# f280049_boost_robotics.net
KiCad netlist of a schematic drawn in EAGLE
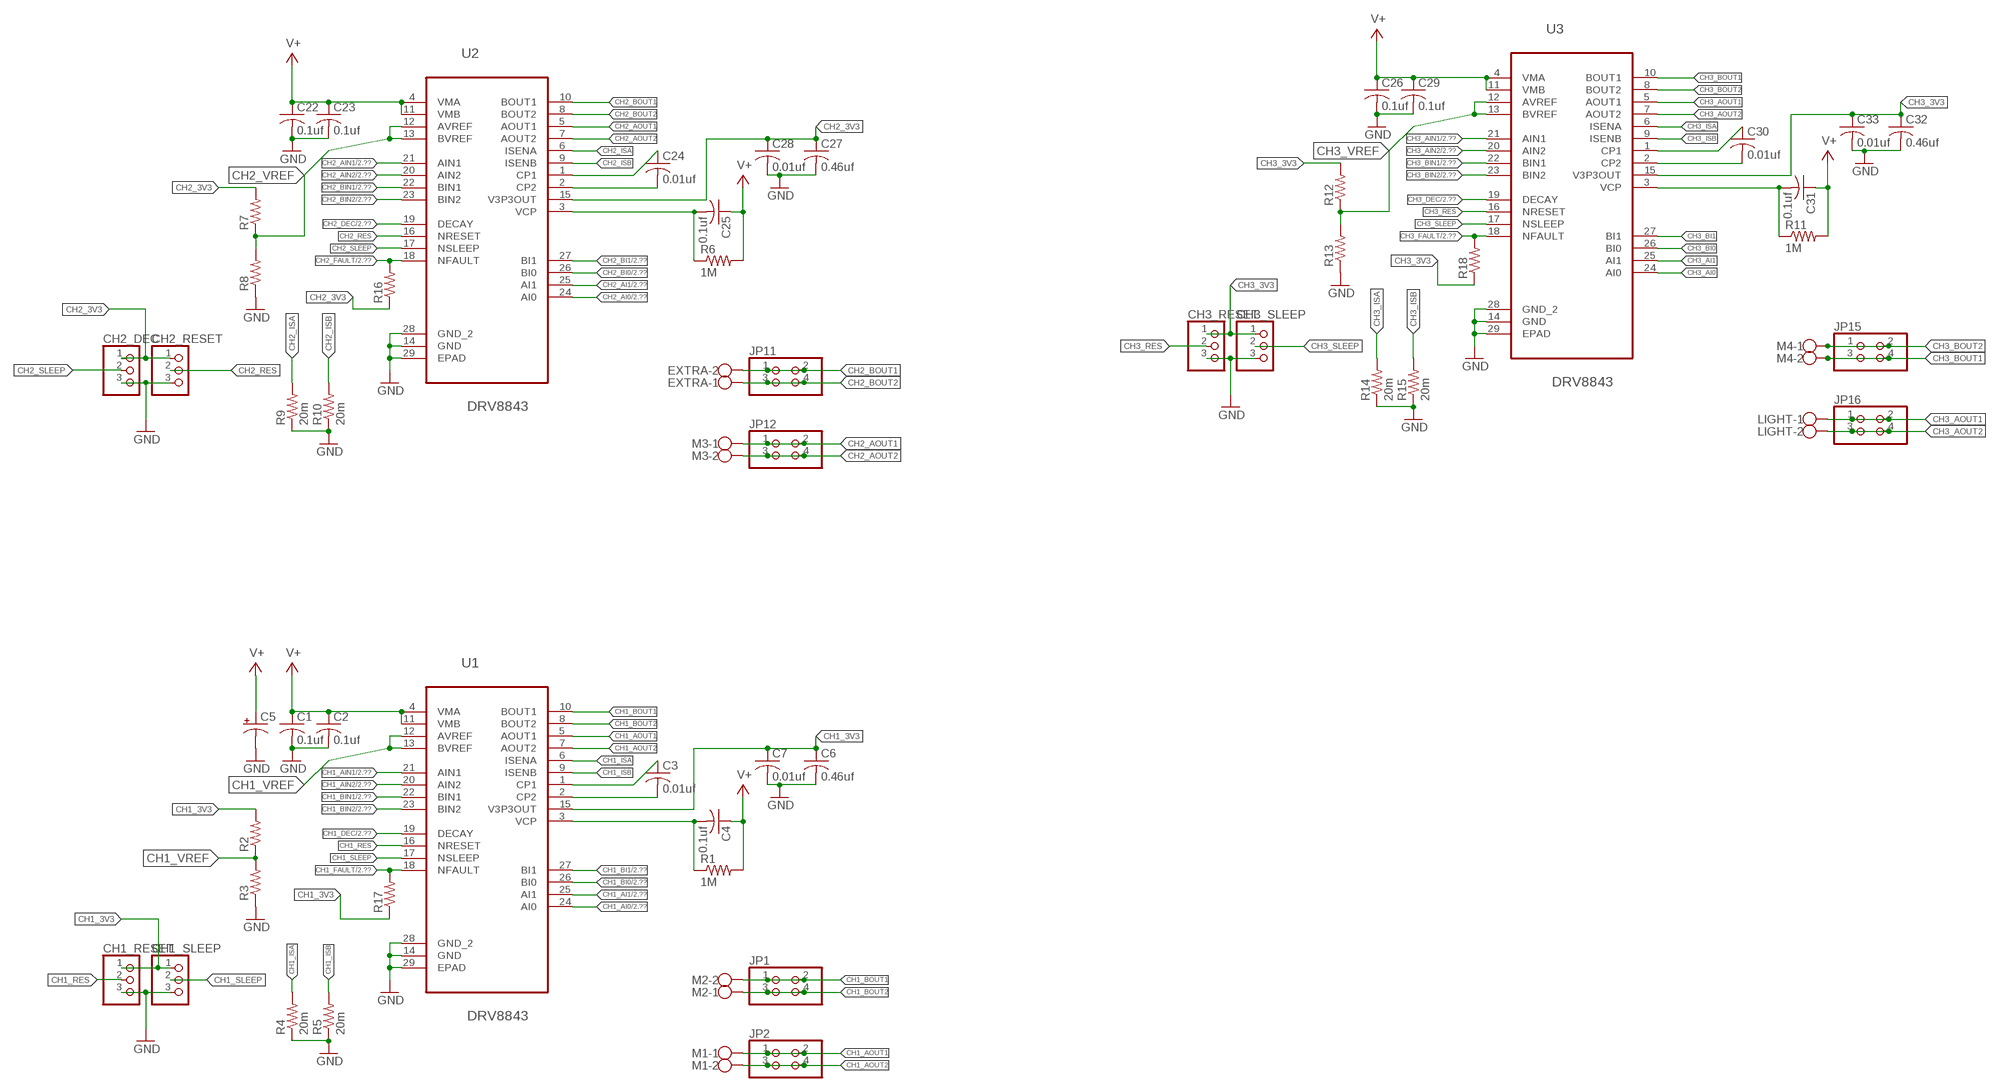
[diagram p0: schematic, sheet 1]
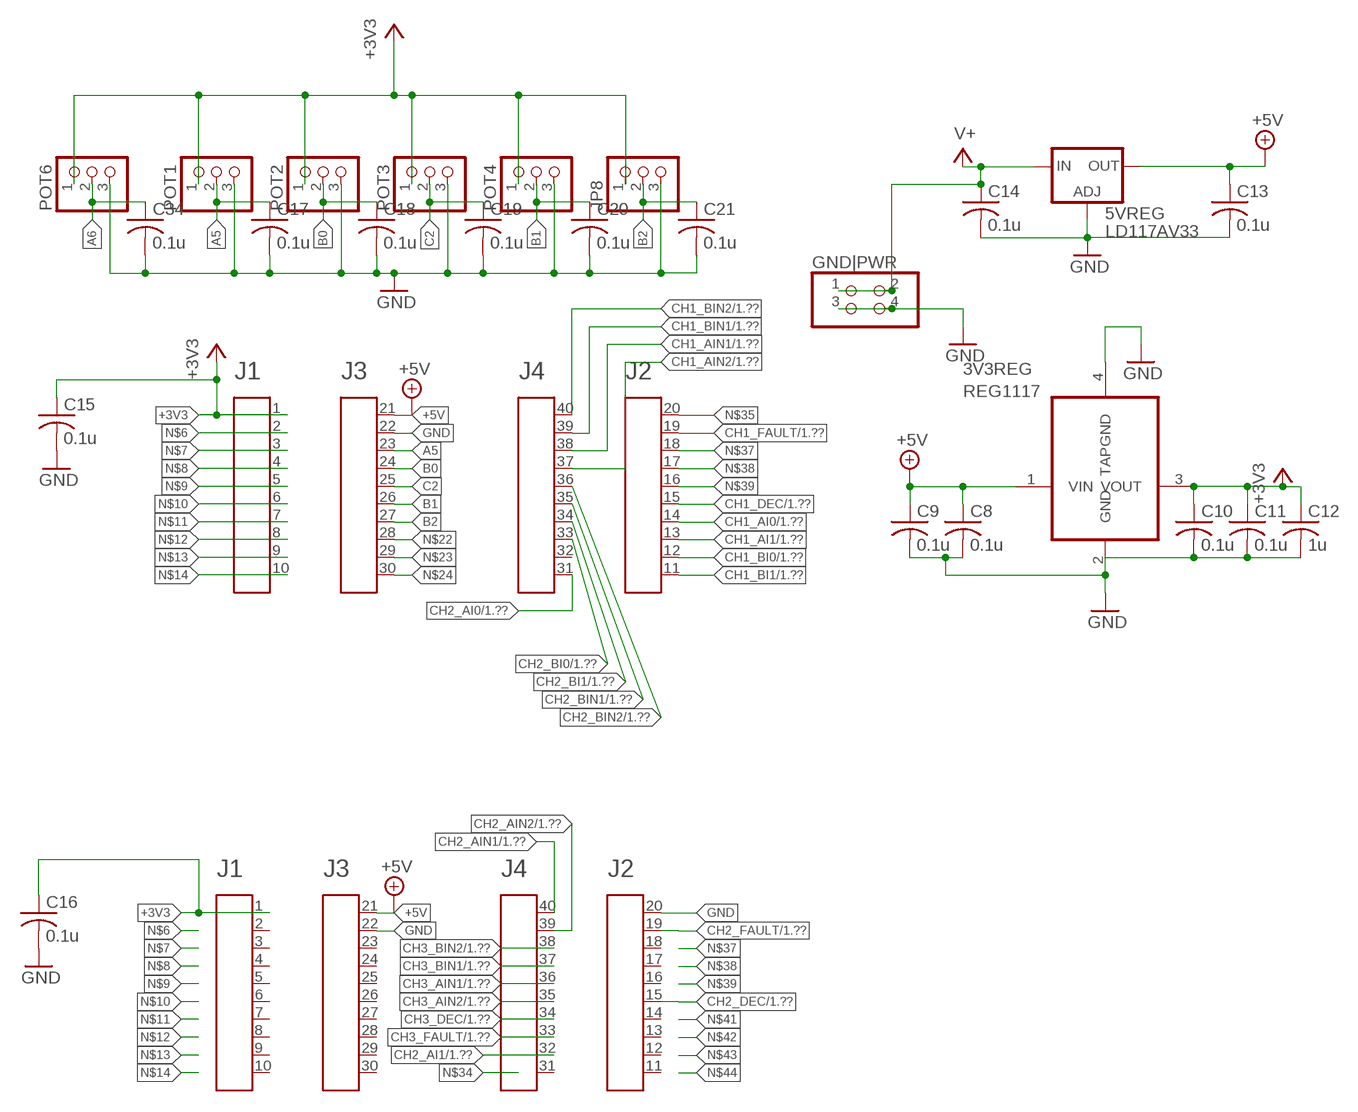
[diagram p1: schematic, sheet 2]

(export (version "E")
  (design (tool "Eeschema 10.0.6"))
  (components
    (comp (ref "3V3REG")
      (value "REG1117")
      (footprint "eagle-import:SOT223")
      (libsource (lib "eagle-import") (part "REG1117"))
    )
    (comp (ref "5VREG")
      (value "LD117AV33")
      (footprint "eagle-import:TO220L1")
      (libsource (lib "eagle-import") (part "LD117A?V33"))
    )
    (comp (ref "A1")
      (value "HEADER4X10-BOOSTERPACK")
      (footprint "eagle-import:4X10-BOOSTERPACK")
      (libsource (lib "eagle-import") (part "HEADER4X10-BOOSTERPACK"))
    )
    (comp (ref "A2")
      (value "HEADER4X10-BOOSTERPACK")
      (footprint "eagle-import:4X10-BOOSTERPACK")
      (libsource (lib "eagle-import") (part "HEADER4X10-BOOSTERPACK"))
    )
    (comp (ref "C8")
      (value "0.1u")
      (footprint "eagle-import:C0603K")
      (libsource (lib "eagle-import") (part "C-USC0603K"))
    )
    (comp (ref "C9")
      (value "0.1u")
      (footprint "eagle-import:C0603K")
      (libsource (lib "eagle-import") (part "C-USC0603K"))
    )
    (comp (ref "C10")
      (value "0.1u")
      (footprint "eagle-import:C0603K")
      (libsource (lib "eagle-import") (part "C-USC0603K"))
    )
    (comp (ref "C11")
      (value "0.1u")
      (footprint "eagle-import:C0603K")
      (libsource (lib "eagle-import") (part "C-USC0603K"))
    )
    (comp (ref "C12")
      (value "1u")
      (footprint "eagle-import:C0805K")
      (libsource (lib "eagle-import") (part "C-USC0805K"))
    )
    (comp (ref "C13")
      (value "0.1u")
      (footprint "eagle-import:C0603K")
      (libsource (lib "eagle-import") (part "C-USC0603K"))
    )
    (comp (ref "C14")
      (value "0.1u")
      (footprint "eagle-import:C0603K")
      (libsource (lib "eagle-import") (part "C-USC0603K"))
    )
    (comp (ref "C15")
      (value "0.1u")
      (footprint "eagle-import:C0603K")
      (libsource (lib "eagle-import") (part "C-USC0603K"))
    )
    (comp (ref "C16")
      (value "0.1u")
      (footprint "eagle-import:C0603K")
      (libsource (lib "eagle-import") (part "C-USC0603K"))
    )
    (comp (ref "C17")
      (value "0.1u")
      (footprint "eagle-import:C0603K")
      (libsource (lib "eagle-import") (part "C-USC0603K"))
    )
    (comp (ref "C18")
      (value "0.1u")
      (footprint "eagle-import:C0603K")
      (libsource (lib "eagle-import") (part "C-USC0603K"))
    )
    (comp (ref "C19")
      (value "0.1u")
      (footprint "eagle-import:C0603K")
      (libsource (lib "eagle-import") (part "C-USC0603K"))
    )
    (comp (ref "C20")
      (value "0.1u")
      (footprint "eagle-import:C0603K")
      (libsource (lib "eagle-import") (part "C-USC0603K"))
    )
    (comp (ref "C21")
      (value "0.1u")
      (footprint "eagle-import:C0603K")
      (libsource (lib "eagle-import") (part "C-USC0603K"))
    )
    (comp (ref "C34")
      (value "0.1u")
      (footprint "eagle-import:C0603K")
      (libsource (lib "eagle-import") (part "C-USC0603K"))
    )
    (comp (ref "GND|PWR")
      (value "PINHD-2X2")
      (footprint "eagle-import:2X02")
      (libsource (lib "eagle-import") (part "PINHD-2X2"))
    )
    (comp (ref "JP8")
      (value "PINHD-1X3")
      (footprint "eagle-import:1X03")
      (libsource (lib "eagle-import") (part "PINHD-1X3"))
    )
    (comp (ref "POT1")
      (value "PINHD-1X3")
      (footprint "eagle-import:1X03")
      (libsource (lib "eagle-import") (part "PINHD-1X3"))
    )
    (comp (ref "POT2")
      (value "PINHD-1X3")
      (footprint "eagle-import:1X03")
      (libsource (lib "eagle-import") (part "PINHD-1X3"))
    )
    (comp (ref "POT3")
      (value "PINHD-1X3")
      (footprint "eagle-import:1X03")
      (libsource (lib "eagle-import") (part "PINHD-1X3"))
    )
    (comp (ref "POT4")
      (value "PINHD-1X3")
      (footprint "eagle-import:1X03")
      (libsource (lib "eagle-import") (part "PINHD-1X3"))
    )
    (comp (ref "POT6")
      (value "PINHD-1X3")
      (footprint "eagle-import:1X03")
      (libsource (lib "eagle-import") (part "PINHD-1X3"))
    )
    (comp (ref "C1")
      (value "0.1uf")
      (footprint "eagle-import:C0603K")
      (libsource (lib "eagle-import") (part "C-USC0603K"))
    )
    (comp (ref "C2")
      (value "0.1uf")
      (footprint "eagle-import:C0603K")
      (libsource (lib "eagle-import") (part "C-USC0603K"))
    )
    (comp (ref "C3")
      (value "0.01uf")
      (footprint "eagle-import:C0603K")
      (libsource (lib "eagle-import") (part "C-USC0603K"))
    )
    (comp (ref "C4")
      (value "0.1uf")
      (footprint "eagle-import:C0603K")
      (libsource (lib "eagle-import") (part "C-USC0603K"))
    )
    (comp (ref "C5")
      (value "CPOL-USE5-8.5")
      (footprint "eagle-import:E5-8,5")
      (libsource (lib "eagle-import") (part "CPOL-USE5-8.5"))
    )
    (comp (ref "C6")
      (value "0.46uf")
      (footprint "eagle-import:C0603K")
      (libsource (lib "eagle-import") (part "C-USC0603K"))
    )
    (comp (ref "C7")
      (value "0.01uf")
      (footprint "eagle-import:C0603K")
      (libsource (lib "eagle-import") (part "C-USC0603K"))
    )
    (comp (ref "C22")
      (value "0.1uf")
      (footprint "eagle-import:C0603K")
      (libsource (lib "eagle-import") (part "C-USC0603K"))
    )
    (comp (ref "C23")
      (value "0.1uf")
      (footprint "eagle-import:C0603K")
      (libsource (lib "eagle-import") (part "C-USC0603K"))
    )
    (comp (ref "C24")
      (value "0.01uf")
      (footprint "eagle-import:C0603K")
      (libsource (lib "eagle-import") (part "C-USC0603K"))
    )
    (comp (ref "C25")
      (value "0.1uf")
      (footprint "eagle-import:C0603K")
      (libsource (lib "eagle-import") (part "C-USC0603K"))
    )
    (comp (ref "C26")
      (value "0.1uf")
      (footprint "eagle-import:C0603K")
      (libsource (lib "eagle-import") (part "C-USC0603K"))
    )
    (comp (ref "C27")
      (value "0.46uf")
      (footprint "eagle-import:C0603K")
      (libsource (lib "eagle-import") (part "C-USC0603K"))
    )
    (comp (ref "C28")
      (value "0.01uf")
      (footprint "eagle-import:C0603K")
      (libsource (lib "eagle-import") (part "C-USC0603K"))
    )
    (comp (ref "C29")
      (value "0.1uf")
      (footprint "eagle-import:C0603K")
      (libsource (lib "eagle-import") (part "C-USC0603K"))
    )
    (comp (ref "C30")
      (value "0.01uf")
      (footprint "eagle-import:C0603K")
      (libsource (lib "eagle-import") (part "C-USC0603K"))
    )
    (comp (ref "C31")
      (value "0.1uf")
      (footprint "eagle-import:C0603K")
      (libsource (lib "eagle-import") (part "C-USC0603K"))
    )
    (comp (ref "C32")
      (value "0.46uf")
      (footprint "eagle-import:C0603K")
      (libsource (lib "eagle-import") (part "C-USC0603K"))
    )
    (comp (ref "C33")
      (value "0.01uf")
      (footprint "eagle-import:C0603K")
      (libsource (lib "eagle-import") (part "C-USC0603K"))
    )
    (comp (ref "CH1_RESET")
      (value "PINHD-1X3")
      (footprint "eagle-import:1X03")
      (libsource (lib "eagle-import") (part "PINHD-1X3"))
    )
    (comp (ref "CH1_SLEEP")
      (value "PINHD-1X3")
      (footprint "eagle-import:1X03")
      (libsource (lib "eagle-import") (part "PINHD-1X3"))
    )
    (comp (ref "CH2_DEC")
      (value "PINHD-1X3")
      (footprint "eagle-import:1X03")
      (libsource (lib "eagle-import") (part "PINHD-1X3"))
    )
    (comp (ref "CH2_RESET")
      (value "PINHD-1X3")
      (footprint "eagle-import:1X03")
      (libsource (lib "eagle-import") (part "PINHD-1X3"))
    )
    (comp (ref "CH3_RESET")
      (value "PINHD-1X3")
      (footprint "eagle-import:1X03")
      (libsource (lib "eagle-import") (part "PINHD-1X3"))
    )
    (comp (ref "CH3_SLEEP")
      (value "PINHD-1X3")
      (footprint "eagle-import:1X03")
      (libsource (lib "eagle-import") (part "PINHD-1X3"))
    )
    (comp (ref "EXTRA")
      (value "W237-102")
      (footprint "eagle-import:W237-102")
      (fields (field (name "MPN") "237-102"))
      (libsource (lib "eagle-import") (part "W237-102"))
    )
    (comp (ref "JP1")
      (value "PINHD-2X2")
      (footprint "eagle-import:2X02")
      (libsource (lib "eagle-import") (part "PINHD-2X2"))
    )
    (comp (ref "JP2")
      (value "PINHD-2X2")
      (footprint "eagle-import:2X02")
      (libsource (lib "eagle-import") (part "PINHD-2X2"))
    )
    (comp (ref "JP11")
      (value "PINHD-2X2")
      (footprint "eagle-import:2X02")
      (libsource (lib "eagle-import") (part "PINHD-2X2"))
    )
    (comp (ref "JP12")
      (value "PINHD-2X2")
      (footprint "eagle-import:2X02")
      (libsource (lib "eagle-import") (part "PINHD-2X2"))
    )
    (comp (ref "JP15")
      (value "PINHD-2X2")
      (footprint "eagle-import:2X02")
      (libsource (lib "eagle-import") (part "PINHD-2X2"))
    )
    (comp (ref "JP16")
      (value "PINHD-2X2")
      (footprint "eagle-import:2X02")
      (libsource (lib "eagle-import") (part "PINHD-2X2"))
    )
    (comp (ref "LIGHT")
      (value "W237-102")
      (footprint "eagle-import:W237-102")
      (fields (field (name "MPN") "237-102"))
      (libsource (lib "eagle-import") (part "W237-102"))
    )
    (comp (ref "M1")
      (value "W237-102")
      (footprint "eagle-import:W237-102")
      (fields (field (name "MPN") "237-102"))
      (libsource (lib "eagle-import") (part "W237-102"))
    )
    (comp (ref "M2")
      (value "W237-102")
      (footprint "eagle-import:W237-102")
      (fields (field (name "MPN") "237-102"))
      (libsource (lib "eagle-import") (part "W237-102"))
    )
    (comp (ref "M3")
      (value "W237-102")
      (footprint "eagle-import:W237-102")
      (fields (field (name "MPN") "237-102"))
      (libsource (lib "eagle-import") (part "W237-102"))
    )
    (comp (ref "M4")
      (value "W237-102")
      (footprint "eagle-import:W237-102")
      (fields (field (name "MPN") "237-102"))
      (libsource (lib "eagle-import") (part "W237-102"))
    )
    (comp (ref "R1")
      (value "1M")
      (footprint "eagle-import:R0402")
      (libsource (lib "eagle-import") (part "R-US_R0402"))
    )
    (comp (ref "R2")
      (value "R-US_R0402")
      (footprint "eagle-import:R0402")
      (libsource (lib "eagle-import") (part "R-US_R0402"))
    )
    (comp (ref "R3")
      (value "R-US_R0402")
      (footprint "eagle-import:R0402")
      (libsource (lib "eagle-import") (part "R-US_R0402"))
    )
    (comp (ref "R4")
      (value "20m")
      (footprint "eagle-import:R0402")
      (libsource (lib "eagle-import") (part "R-US_R0402"))
    )
    (comp (ref "R5")
      (value "20m")
      (footprint "eagle-import:R0402")
      (libsource (lib "eagle-import") (part "R-US_R0402"))
    )
    (comp (ref "R6")
      (value "1M")
      (footprint "eagle-import:R0402")
      (libsource (lib "eagle-import") (part "R-US_R0402"))
    )
    (comp (ref "R7")
      (value "R-US_R0402")
      (footprint "eagle-import:R0402")
      (libsource (lib "eagle-import") (part "R-US_R0402"))
    )
    (comp (ref "R8")
      (value "R-US_R0402")
      (footprint "eagle-import:R0402")
      (libsource (lib "eagle-import") (part "R-US_R0402"))
    )
    (comp (ref "R9")
      (value "20m")
      (footprint "eagle-import:R0402")
      (libsource (lib "eagle-import") (part "R-US_R0402"))
    )
    (comp (ref "R10")
      (value "20m")
      (footprint "eagle-import:R0402")
      (libsource (lib "eagle-import") (part "R-US_R0402"))
    )
    (comp (ref "R11")
      (value "1M")
      (footprint "eagle-import:R0402")
      (libsource (lib "eagle-import") (part "R-US_R0402"))
    )
    (comp (ref "R12")
      (value "R-US_R0402")
      (footprint "eagle-import:R0402")
      (libsource (lib "eagle-import") (part "R-US_R0402"))
    )
    (comp (ref "R13")
      (value "R-US_R0402")
      (footprint "eagle-import:R0402")
      (libsource (lib "eagle-import") (part "R-US_R0402"))
    )
    (comp (ref "R14")
      (value "20m")
      (footprint "eagle-import:R0402")
      (libsource (lib "eagle-import") (part "R-US_R0402"))
    )
    (comp (ref "R15")
      (value "20m")
      (footprint "eagle-import:R0402")
      (libsource (lib "eagle-import") (part "R-US_R0402"))
    )
    (comp (ref "R16")
      (value "R-US_R0402")
      (footprint "eagle-import:R0402")
      (libsource (lib "eagle-import") (part "R-US_R0402"))
    )
    (comp (ref "R17")
      (value "R-US_R0402")
      (footprint "eagle-import:R0402")
      (libsource (lib "eagle-import") (part "R-US_R0402"))
    )
    (comp (ref "R18")
      (value "R-US_R0402")
      (footprint "eagle-import:R0402")
      (libsource (lib "eagle-import") (part "R-US_R0402"))
    )
    (comp (ref "U1")
      (value "DRV8843")
      (footprint "eagle-import:SOP65P640X120-29N")
      (fields (field (name "MPN") "DRV8828PWP"))
      (libsource (lib "eagle-import") (part "DRV8843"))
    )
    (comp (ref "U2")
      (value "DRV8843")
      (footprint "eagle-import:SOP65P640X120-29N")
      (fields (field (name "MPN") "DRV8828PWP"))
      (libsource (lib "eagle-import") (part "DRV8843"))
    )
    (comp (ref "U3")
      (value "DRV8843")
      (footprint "eagle-import:SOP65P640X120-29N")
      (fields (field (name "MPN") "DRV8828PWP"))
      (libsource (lib "eagle-import") (part "DRV8843"))
    )
  )
  (nets
    (net (code "1") (name "+3V3") (class "Default")
      (node (ref "3V3REG") (pin "3") (pinfunction "VOUT_3") (pintype "output"))
      (node (ref "A1") (pin "1") (pinfunction "P$1_1") (pintype "bidirectional"))
      (node (ref "A2") (pin "1") (pinfunction "P$1_1") (pintype "bidirectional"))
      (node (ref "C10") (pin "1") (pinfunction "1_1") (pintype "passive"))
      (node (ref "C11") (pin "1") (pinfunction "1_1") (pintype "passive"))
      (node (ref "C12") (pin "1") (pinfunction "1_1") (pintype "passive"))
      (node (ref "C15") (pin "1") (pinfunction "1_1") (pintype "passive"))
      (node (ref "C16") (pin "1") (pinfunction "1_1") (pintype "passive"))
      (node (ref "JP8") (pin "1") (pinfunction "1_1") (pintype "passive"))
      (node (ref "POT1") (pin "1") (pinfunction "1_1") (pintype "passive"))
      (node (ref "POT2") (pin "1") (pinfunction "1_1") (pintype "passive"))
      (node (ref "POT3") (pin "1") (pinfunction "1_1") (pintype "passive"))
      (node (ref "POT4") (pin "1") (pinfunction "1_1") (pintype "passive"))
      (node (ref "POT6") (pin "1") (pinfunction "1_1") (pintype "passive"))
    )
    (net (code "2") (name "+5V") (class "Default")
      (node (ref "3V3REG") (pin "1") (pinfunction "VIN_1") (pintype "input"))
      (node (ref "5VREG") (pin "2") (pinfunction "OUT_2") (pintype "passive"))
      (node (ref "A1") (pin "21") (pinfunction "P$21_21") (pintype "bidirectional"))
      (node (ref "A2") (pin "21") (pinfunction "P$21_21") (pintype "bidirectional"))
      (node (ref "C13") (pin "1") (pinfunction "1_1") (pintype "passive"))
      (node (ref "C8") (pin "1") (pinfunction "1_1") (pintype "passive"))
      (node (ref "C9") (pin "1") (pinfunction "1_1") (pintype "passive"))
    )
    (net (code "3") (name "A5") (class "Default")
      (node (ref "A2") (pin "23") (pinfunction "P$23_23") (pintype "bidirectional"))
      (node (ref "C17") (pin "1") (pinfunction "1_1") (pintype "passive"))
      (node (ref "POT1") (pin "2") (pinfunction "2_2") (pintype "passive"))
    )
    (net (code "4") (name "A6") (class "Default")
      (node (ref "C34") (pin "1") (pinfunction "1_1") (pintype "passive"))
      (node (ref "POT6") (pin "2") (pinfunction "2_2") (pintype "passive"))
    )
    (net (code "5") (name "B0") (class "Default")
      (node (ref "A2") (pin "24") (pinfunction "P$24_24") (pintype "bidirectional"))
      (node (ref "C18") (pin "1") (pinfunction "1_1") (pintype "passive"))
      (node (ref "POT2") (pin "2") (pinfunction "2_2") (pintype "passive"))
    )
    (net (code "6") (name "B1") (class "Default")
      (node (ref "A2") (pin "26") (pinfunction "P$26_26") (pintype "bidirectional"))
      (node (ref "C20") (pin "1") (pinfunction "1_1") (pintype "passive"))
      (node (ref "POT4") (pin "2") (pinfunction "2_2") (pintype "passive"))
    )
    (net (code "7") (name "B2") (class "Default")
      (node (ref "A2") (pin "27") (pinfunction "P$27_27") (pintype "bidirectional"))
      (node (ref "C21") (pin "1") (pinfunction "1_1") (pintype "passive"))
      (node (ref "JP8") (pin "2") (pinfunction "2_2") (pintype "passive"))
    )
    (net (code "8") (name "C2") (class "Default")
      (node (ref "A2") (pin "25") (pinfunction "P$25_25") (pintype "bidirectional"))
      (node (ref "C19") (pin "1") (pinfunction "1_1") (pintype "passive"))
      (node (ref "POT3") (pin "2") (pinfunction "2_2") (pintype "passive"))
    )
    (net (code "9") (name "CH1_3V3") (class "Default")
      (node (ref "C6") (pin "1") (pinfunction "1_1") (pintype "passive"))
      (node (ref "C7") (pin "1") (pinfunction "1_1") (pintype "passive"))
      (node (ref "CH1_RESET") (pin "1") (pinfunction "1_1") (pintype "passive"))
      (node (ref "CH1_SLEEP") (pin "1") (pinfunction "1_1") (pintype "passive"))
      (node (ref "R17") (pin "1") (pinfunction "1_1") (pintype "passive"))
      (node (ref "R2") (pin "2") (pinfunction "2_2") (pintype "passive"))
      (node (ref "U1") (pin "15") (pinfunction "V3P3OUT_15") (pintype "output"))
    )
    (net (code "10") (name "CH1_AI0") (class "Default")
      (node (ref "A2") (pin "14") (pinfunction "P$14_14") (pintype "bidirectional"))
      (node (ref "U1") (pin "24") (pinfunction "AI0_24") (pintype "bidirectional"))
    )
    (net (code "11") (name "CH1_AI1") (class "Default")
      (node (ref "A2") (pin "13") (pinfunction "P$13_13") (pintype "bidirectional"))
      (node (ref "U1") (pin "25") (pinfunction "AI1_25") (pintype "bidirectional"))
    )
    (net (code "12") (name "CH1_AIN1") (class "Default")
      (node (ref "A2") (pin "38") (pinfunction "P$38_38") (pintype "bidirectional"))
      (node (ref "U1") (pin "21") (pinfunction "AIN1_21") (pintype "bidirectional"))
    )
    (net (code "13") (name "CH1_AIN2") (class "Default")
      (node (ref "A2") (pin "37") (pinfunction "P$37_37") (pintype "bidirectional"))
      (node (ref "U1") (pin "20") (pinfunction "AIN2_20") (pintype "bidirectional"))
    )
    (net (code "14") (name "CH1_AOUT1") (class "Default")
      (node (ref "JP2") (pin "1") (pinfunction "1_1") (pintype "passive"))
      (node (ref "JP2") (pin "2") (pinfunction "2_2") (pintype "passive"))
      (node (ref "M1") (pin "1") (pinfunction "KL_1") (pintype "passive"))
      (node (ref "U1") (pin "5") (pinfunction "AOUT1_5") (pintype "output"))
    )
    (net (code "15") (name "CH1_AOUT2") (class "Default")
      (node (ref "JP2") (pin "3") (pinfunction "3_3") (pintype "passive"))
      (node (ref "JP2") (pin "4") (pinfunction "4_4") (pintype "passive"))
      (node (ref "M1") (pin "2") (pinfunction "KL_2") (pintype "passive"))
      (node (ref "U1") (pin "7") (pinfunction "AOUT2_7") (pintype "output"))
    )
    (net (code "16") (name "CH1_BI0") (class "Default")
      (node (ref "A2") (pin "12") (pinfunction "P$12_12") (pintype "bidirectional"))
      (node (ref "U1") (pin "26") (pinfunction "BI0_26") (pintype "bidirectional"))
    )
    (net (code "17") (name "CH1_BI1") (class "Default")
      (node (ref "A2") (pin "11") (pinfunction "P$11_11") (pintype "bidirectional"))
      (node (ref "U1") (pin "27") (pinfunction "BI1_27") (pintype "bidirectional"))
    )
    (net (code "18") (name "CH1_BIN1") (class "Default")
      (node (ref "A2") (pin "39") (pinfunction "P$39_39") (pintype "bidirectional"))
      (node (ref "U1") (pin "22") (pinfunction "BIN1_22") (pintype "bidirectional"))
    )
    (net (code "19") (name "CH1_BIN2") (class "Default")
      (node (ref "A2") (pin "40") (pinfunction "P$40_40") (pintype "bidirectional"))
      (node (ref "U1") (pin "23") (pinfunction "BIN2_23") (pintype "bidirectional"))
    )
    (net (code "20") (name "CH1_BOUT1") (class "Default")
      (node (ref "JP1") (pin "1") (pinfunction "1_1") (pintype "passive"))
      (node (ref "JP1") (pin "2") (pinfunction "2_2") (pintype "passive"))
      (node (ref "M2") (pin "2") (pinfunction "KL_2") (pintype "passive"))
      (node (ref "U1") (pin "10") (pinfunction "BOUT1_10") (pintype "output"))
    )
    (net (code "21") (name "CH1_BOUT2") (class "Default")
      (node (ref "JP1") (pin "3") (pinfunction "3_3") (pintype "passive"))
      (node (ref "JP1") (pin "4") (pinfunction "4_4") (pintype "passive"))
      (node (ref "M2") (pin "1") (pinfunction "KL_1") (pintype "passive"))
      (node (ref "U1") (pin "8") (pinfunction "BOUT2_8") (pintype "output"))
    )
    (net (code "22") (name "CH1_DEC") (class "Default")
      (node (ref "A2") (pin "15") (pinfunction "P$15_15") (pintype "bidirectional"))
      (node (ref "U1") (pin "19") (pinfunction "DECAY_19") (pintype "input"))
    )
    (net (code "23") (name "CH1_FAULT") (class "Default")
      (node (ref "A2") (pin "19") (pinfunction "P$19_19") (pintype "bidirectional"))
      (node (ref "R17") (pin "2") (pinfunction "2_2") (pintype "passive"))
      (node (ref "U1") (pin "18") (pinfunction "NFAULT_18") (pintype "input"))
    )
    (net (code "24") (name "CH1_ISA") (class "Default")
      (node (ref "R4") (pin "2") (pinfunction "2_2") (pintype "passive"))
      (node (ref "U1") (pin "6") (pinfunction "ISENA_6") (pintype "bidirectional"))
    )
    (net (code "25") (name "CH1_ISB") (class "Default")
      (node (ref "R5") (pin "2") (pinfunction "2_2") (pintype "passive"))
      (node (ref "U1") (pin "9") (pinfunction "ISENB_9") (pintype "bidirectional"))
    )
    (net (code "26") (name "CH1_RES") (class "Default")
      (node (ref "CH1_RESET") (pin "2") (pinfunction "2_2") (pintype "passive"))
      (node (ref "U1") (pin "16") (pinfunction "NRESET_16") (pintype "input"))
    )
    (net (code "27") (name "CH1_SLEEP") (class "Default")
      (node (ref "CH1_SLEEP") (pin "2") (pinfunction "2_2") (pintype "passive"))
      (node (ref "U1") (pin "17") (pinfunction "NSLEEP_17") (pintype "input"))
    )
    (net (code "28") (name "CH1_VREF") (class "Default")
      (node (ref "R2") (pin "1") (pinfunction "1_1") (pintype "passive"))
      (node (ref "R3") (pin "2") (pinfunction "2_2") (pintype "passive"))
      (node (ref "U1") (pin "12") (pinfunction "AVREF_12") (pintype "input"))
      (node (ref "U1") (pin "13") (pinfunction "BVREF_13") (pintype "input"))
    )
    (net (code "29") (name "CH2_3V3") (class "Default")
      (node (ref "C27") (pin "1") (pinfunction "1_1") (pintype "passive"))
      (node (ref "C28") (pin "1") (pinfunction "1_1") (pintype "passive"))
      (node (ref "CH2_DEC") (pin "1") (pinfunction "1_1") (pintype "passive"))
      (node (ref "CH2_RESET") (pin "1") (pinfunction "1_1") (pintype "passive"))
      (node (ref "R16") (pin "1") (pinfunction "1_1") (pintype "passive"))
      (node (ref "R7") (pin "2") (pinfunction "2_2") (pintype "passive"))
      (node (ref "U2") (pin "15") (pinfunction "V3P3OUT_15") (pintype "output"))
    )
    (net (code "30") (name "CH2_AI0") (class "Default")
      (node (ref "A2") (pin "31") (pinfunction "P$31_31") (pintype "bidirectional"))
      (node (ref "U2") (pin "24") (pinfunction "AI0_24") (pintype "bidirectional"))
    )
    (net (code "31") (name "CH2_AI1") (class "Default")
      (node (ref "A1") (pin "32") (pinfunction "P$32_32") (pintype "bidirectional"))
      (node (ref "U2") (pin "25") (pinfunction "AI1_25") (pintype "bidirectional"))
    )
    (net (code "32") (name "CH2_AIN1") (class "Default")
      (node (ref "A1") (pin "40") (pinfunction "P$40_40") (pintype "bidirectional"))
      (node (ref "U2") (pin "21") (pinfunction "AIN1_21") (pintype "bidirectional"))
    )
    (net (code "33") (name "CH2_AIN2") (class "Default")
      (node (ref "A1") (pin "39") (pinfunction "P$39_39") (pintype "bidirectional"))
      (node (ref "U2") (pin "20") (pinfunction "AIN2_20") (pintype "bidirectional"))
    )
    (net (code "34") (name "CH2_AOUT1") (class "Default")
      (node (ref "JP12") (pin "1") (pinfunction "1_1") (pintype "passive"))
      (node (ref "JP12") (pin "2") (pinfunction "2_2") (pintype "passive"))
      (node (ref "M3") (pin "1") (pinfunction "KL_1") (pintype "passive"))
      (node (ref "U2") (pin "5") (pinfunction "AOUT1_5") (pintype "output"))
    )
    (net (code "35") (name "CH2_AOUT2") (class "Default")
      (node (ref "JP12") (pin "3") (pinfunction "3_3") (pintype "passive"))
      (node (ref "JP12") (pin "4") (pinfunction "4_4") (pintype "passive"))
      (node (ref "M3") (pin "2") (pinfunction "KL_2") (pintype "passive"))
      (node (ref "U2") (pin "7") (pinfunction "AOUT2_7") (pintype "output"))
    )
    (net (code "36") (name "CH2_BI0") (class "Default")
      (node (ref "A2") (pin "33") (pinfunction "P$33_33") (pintype "bidirectional"))
      (node (ref "U2") (pin "26") (pinfunction "BI0_26") (pintype "bidirectional"))
    )
    (net (code "37") (name "CH2_BI1") (class "Default")
      (node (ref "A2") (pin "34") (pinfunction "P$34_34") (pintype "bidirectional"))
      (node (ref "U2") (pin "27") (pinfunction "BI1_27") (pintype "bidirectional"))
    )
    (net (code "38") (name "CH2_BIN1") (class "Default")
      (node (ref "A2") (pin "35") (pinfunction "P$35_35") (pintype "bidirectional"))
      (node (ref "U2") (pin "22") (pinfunction "BIN1_22") (pintype "bidirectional"))
    )
    (net (code "39") (name "CH2_BIN2") (class "Default")
      (node (ref "A2") (pin "36") (pinfunction "P$36_36") (pintype "bidirectional"))
      (node (ref "U2") (pin "23") (pinfunction "BIN2_23") (pintype "bidirectional"))
    )
    (net (code "40") (name "CH2_BOUT1") (class "Default")
      (node (ref "EXTRA") (pin "2") (pinfunction "KL_2") (pintype "passive"))
      (node (ref "JP11") (pin "1") (pinfunction "1_1") (pintype "passive"))
      (node (ref "JP11") (pin "2") (pinfunction "2_2") (pintype "passive"))
      (node (ref "U2") (pin "10") (pinfunction "BOUT1_10") (pintype "output"))
    )
    (net (code "41") (name "CH2_BOUT2") (class "Default")
      (node (ref "EXTRA") (pin "1") (pinfunction "KL_1") (pintype "passive"))
      (node (ref "JP11") (pin "3") (pinfunction "3_3") (pintype "passive"))
      (node (ref "JP11") (pin "4") (pinfunction "4_4") (pintype "passive"))
      (node (ref "U2") (pin "8") (pinfunction "BOUT2_8") (pintype "output"))
    )
    (net (code "42") (name "CH2_DEC") (class "Default")
      (node (ref "A1") (pin "15") (pinfunction "P$15_15") (pintype "bidirectional"))
      (node (ref "U2") (pin "19") (pinfunction "DECAY_19") (pintype "input"))
    )
    (net (code "43") (name "CH2_FAULT") (class "Default")
      (node (ref "A1") (pin "19") (pinfunction "P$19_19") (pintype "bidirectional"))
      (node (ref "R16") (pin "2") (pinfunction "2_2") (pintype "passive"))
      (node (ref "U2") (pin "18") (pinfunction "NFAULT_18") (pintype "input"))
    )
    (net (code "44") (name "CH2_ISA") (class "Default")
      (node (ref "R9") (pin "2") (pinfunction "2_2") (pintype "passive"))
      (node (ref "U2") (pin "6") (pinfunction "ISENA_6") (pintype "bidirectional"))
    )
    (net (code "45") (name "CH2_ISB") (class "Default")
      (node (ref "R10") (pin "2") (pinfunction "2_2") (pintype "passive"))
      (node (ref "U2") (pin "9") (pinfunction "ISENB_9") (pintype "bidirectional"))
    )
    (net (code "46") (name "CH2_RES") (class "Default")
      (node (ref "CH2_RESET") (pin "2") (pinfunction "2_2") (pintype "passive"))
      (node (ref "U2") (pin "16") (pinfunction "NRESET_16") (pintype "input"))
    )
    (net (code "47") (name "CH2_SLEEP") (class "Default")
      (node (ref "CH2_DEC") (pin "2") (pinfunction "2_2") (pintype "passive"))
      (node (ref "U2") (pin "17") (pinfunction "NSLEEP_17") (pintype "input"))
    )
    (net (code "48") (name "CH2_VREF") (class "Default")
      (node (ref "R7") (pin "1") (pinfunction "1_1") (pintype "passive"))
      (node (ref "R8") (pin "2") (pinfunction "2_2") (pintype "passive"))
      (node (ref "U2") (pin "12") (pinfunction "AVREF_12") (pintype "input"))
      (node (ref "U2") (pin "13") (pinfunction "BVREF_13") (pintype "input"))
    )
    (net (code "49") (name "CH3_3V3") (class "Default")
      (node (ref "C32") (pin "1") (pinfunction "1_1") (pintype "passive"))
      (node (ref "C33") (pin "1") (pinfunction "1_1") (pintype "passive"))
      (node (ref "CH3_RESET") (pin "1") (pinfunction "1_1") (pintype "passive"))
      (node (ref "CH3_SLEEP") (pin "1") (pinfunction "1_1") (pintype "passive"))
      (node (ref "R12") (pin "2") (pinfunction "2_2") (pintype "passive"))
      (node (ref "R18") (pin "1") (pinfunction "1_1") (pintype "passive"))
      (node (ref "U3") (pin "15") (pinfunction "V3P3OUT_15") (pintype "output"))
    )
    (net (code "50") (name "CH3_AI0") (class "Default")
      (node (ref "U3") (pin "24") (pinfunction "AI0_24") (pintype "bidirectional"))
    )
    (net (code "51") (name "CH3_AI1") (class "Default")
      (node (ref "U3") (pin "25") (pinfunction "AI1_25") (pintype "bidirectional"))
    )
    (net (code "52") (name "CH3_AIN1") (class "Default")
      (node (ref "A1") (pin "36") (pinfunction "P$36_36") (pintype "bidirectional"))
      (node (ref "U3") (pin "21") (pinfunction "AIN1_21") (pintype "bidirectional"))
    )
    (net (code "53") (name "CH3_AIN2") (class "Default")
      (node (ref "A1") (pin "35") (pinfunction "P$35_35") (pintype "bidirectional"))
      (node (ref "U3") (pin "20") (pinfunction "AIN2_20") (pintype "bidirectional"))
    )
    (net (code "54") (name "CH3_AOUT1") (class "Default")
      (node (ref "JP16") (pin "1") (pinfunction "1_1") (pintype "passive"))
      (node (ref "JP16") (pin "2") (pinfunction "2_2") (pintype "passive"))
      (node (ref "LIGHT") (pin "1") (pinfunction "KL_1") (pintype "passive"))
      (node (ref "U3") (pin "5") (pinfunction "AOUT1_5") (pintype "output"))
    )
    (net (code "55") (name "CH3_AOUT2") (class "Default")
      (node (ref "JP16") (pin "3") (pinfunction "3_3") (pintype "passive"))
      (node (ref "JP16") (pin "4") (pinfunction "4_4") (pintype "passive"))
      (node (ref "LIGHT") (pin "2") (pinfunction "KL_2") (pintype "passive"))
      (node (ref "U3") (pin "7") (pinfunction "AOUT2_7") (pintype "output"))
    )
    (net (code "56") (name "CH3_BI0") (class "Default")
      (node (ref "U3") (pin "26") (pinfunction "BI0_26") (pintype "bidirectional"))
    )
    (net (code "57") (name "CH3_BI1") (class "Default")
      (node (ref "U3") (pin "27") (pinfunction "BI1_27") (pintype "bidirectional"))
    )
    (net (code "58") (name "CH3_BIN1") (class "Default")
      (node (ref "A1") (pin "37") (pinfunction "P$37_37") (pintype "bidirectional"))
      (node (ref "U3") (pin "22") (pinfunction "BIN1_22") (pintype "bidirectional"))
    )
    (net (code "59") (name "CH3_BIN2") (class "Default")
      (node (ref "A1") (pin "38") (pinfunction "P$38_38") (pintype "bidirectional"))
      (node (ref "U3") (pin "23") (pinfunction "BIN2_23") (pintype "bidirectional"))
    )
    (net (code "60") (name "CH3_BOUT1") (class "Default")
      (node (ref "JP15") (pin "3") (pinfunction "3_3") (pintype "passive"))
      (node (ref "JP15") (pin "4") (pinfunction "4_4") (pintype "passive"))
      (node (ref "M4") (pin "2") (pinfunction "KL_2") (pintype "passive"))
      (node (ref "U3") (pin "10") (pinfunction "BOUT1_10") (pintype "output"))
    )
    (net (code "61") (name "CH3_BOUT2") (class "Default")
      (node (ref "JP15") (pin "1") (pinfunction "1_1") (pintype "passive"))
      (node (ref "JP15") (pin "2") (pinfunction "2_2") (pintype "passive"))
      (node (ref "M4") (pin "1") (pinfunction "KL_1") (pintype "passive"))
      (node (ref "U3") (pin "8") (pinfunction "BOUT2_8") (pintype "output"))
    )
    (net (code "62") (name "CH3_DEC") (class "Default")
      (node (ref "A1") (pin "34") (pinfunction "P$34_34") (pintype "bidirectional"))
      (node (ref "U3") (pin "19") (pinfunction "DECAY_19") (pintype "input"))
    )
    (net (code "63") (name "CH3_FAULT") (class "Default")
      (node (ref "A1") (pin "33") (pinfunction "P$33_33") (pintype "bidirectional"))
      (node (ref "R18") (pin "2") (pinfunction "2_2") (pintype "passive"))
      (node (ref "U3") (pin "18") (pinfunction "NFAULT_18") (pintype "input"))
    )
    (net (code "64") (name "CH3_ISA") (class "Default")
      (node (ref "R14") (pin "2") (pinfunction "2_2") (pintype "passive"))
      (node (ref "U3") (pin "6") (pinfunction "ISENA_6") (pintype "bidirectional"))
    )
    (net (code "65") (name "CH3_ISB") (class "Default")
      (node (ref "R15") (pin "2") (pinfunction "2_2") (pintype "passive"))
      (node (ref "U3") (pin "9") (pinfunction "ISENB_9") (pintype "bidirectional"))
    )
    (net (code "66") (name "CH3_RES") (class "Default")
      (node (ref "CH3_RESET") (pin "2") (pinfunction "2_2") (pintype "passive"))
      (node (ref "U3") (pin "16") (pinfunction "NRESET_16") (pintype "input"))
    )
    (net (code "67") (name "CH3_SLEEP") (class "Default")
      (node (ref "CH3_SLEEP") (pin "2") (pinfunction "2_2") (pintype "passive"))
      (node (ref "U3") (pin "17") (pinfunction "NSLEEP_17") (pintype "input"))
    )
    (net (code "68") (name "CH3_VREF") (class "Default")
      (node (ref "R12") (pin "1") (pinfunction "1_1") (pintype "passive"))
      (node (ref "R13") (pin "2") (pinfunction "2_2") (pintype "passive"))
      (node (ref "U3") (pin "12") (pinfunction "AVREF_12") (pintype "input"))
      (node (ref "U3") (pin "13") (pinfunction "BVREF_13") (pintype "input"))
    )
    (net (code "69") (name "GND") (class "Default")
      (node (ref "3V3REG") (pin "2") (pinfunction "GND_2") (pintype "power_in"))
      (node (ref "3V3REG") (pin "4") (pinfunction "TAPGND_4") (pintype "power_in"))
      (node (ref "5VREG") (pin "1") (pinfunction "ADJ_1") (pintype "input"))
      (node (ref "A1") (pin "20") (pinfunction "P$20_20") (pintype "bidirectional"))
      (node (ref "A1") (pin "22") (pinfunction "P$22_22") (pintype "bidirectional"))
      (node (ref "A2") (pin "22") (pinfunction "P$22_22") (pintype "bidirectional"))
      (node (ref "C1") (pin "2") (pinfunction "2_2") (pintype "passive"))
      (node (ref "C10") (pin "2") (pinfunction "2_2") (pintype "passive"))
      (node (ref "C11") (pin "2") (pinfunction "2_2") (pintype "passive"))
      (node (ref "C12") (pin "2") (pinfunction "2_2") (pintype "passive"))
      (node (ref "C13") (pin "2") (pinfunction "2_2") (pintype "passive"))
      (node (ref "C14") (pin "2") (pinfunction "2_2") (pintype "passive"))
      (node (ref "C15") (pin "2") (pinfunction "2_2") (pintype "passive"))
      (node (ref "C16") (pin "2") (pinfunction "2_2") (pintype "passive"))
      (node (ref "C17") (pin "2") (pinfunction "2_2") (pintype "passive"))
      (node (ref "C18") (pin "2") (pinfunction "2_2") (pintype "passive"))
      (node (ref "C19") (pin "2") (pinfunction "2_2") (pintype "passive"))
      (node (ref "C2") (pin "2") (pinfunction "2_2") (pintype "passive"))
      (node (ref "C20") (pin "2") (pinfunction "2_2") (pintype "passive"))
      (node (ref "C21") (pin "2") (pinfunction "2_2") (pintype "passive"))
      (node (ref "C22") (pin "2") (pinfunction "2_2") (pintype "passive"))
      (node (ref "C23") (pin "2") (pinfunction "2_2") (pintype "passive"))
      (node (ref "C26") (pin "2") (pinfunction "2_2") (pintype "passive"))
      (node (ref "C27") (pin "2") (pinfunction "2_2") (pintype "passive"))
      (node (ref "C28") (pin "2") (pinfunction "2_2") (pintype "passive"))
      (node (ref "C29") (pin "2") (pinfunction "2_2") (pintype "passive"))
      (node (ref "C32") (pin "2") (pinfunction "2_2") (pintype "passive"))
      (node (ref "C33") (pin "2") (pinfunction "2_2") (pintype "passive"))
      (node (ref "C34") (pin "2") (pinfunction "2_2") (pintype "passive"))
      (node (ref "C5") (pin "-") (pinfunction "-_-") (pintype "passive"))
      (node (ref "C6") (pin "2") (pinfunction "2_2") (pintype "passive"))
      (node (ref "C7") (pin "2") (pinfunction "2_2") (pintype "passive"))
      (node (ref "C8") (pin "2") (pinfunction "2_2") (pintype "passive"))
      (node (ref "C9") (pin "2") (pinfunction "2_2") (pintype "passive"))
      (node (ref "CH1_RESET") (pin "3") (pinfunction "3_3") (pintype "passive"))
      (node (ref "CH1_SLEEP") (pin "3") (pinfunction "3_3") (pintype "passive"))
      (node (ref "CH2_DEC") (pin "3") (pinfunction "3_3") (pintype "passive"))
      (node (ref "CH2_RESET") (pin "3") (pinfunction "3_3") (pintype "passive"))
      (node (ref "CH3_RESET") (pin "3") (pinfunction "3_3") (pintype "passive"))
      (node (ref "CH3_SLEEP") (pin "3") (pinfunction "3_3") (pintype "passive"))
      (node (ref "GND|PWR") (pin "3") (pinfunction "3_3") (pintype "passive"))
      (node (ref "GND|PWR") (pin "4") (pinfunction "4_4") (pintype "passive"))
      (node (ref "JP8") (pin "3") (pinfunction "3_3") (pintype "passive"))
      (node (ref "POT1") (pin "3") (pinfunction "3_3") (pintype "passive"))
      (node (ref "POT2") (pin "3") (pinfunction "3_3") (pintype "passive"))
      (node (ref "POT3") (pin "3") (pinfunction "3_3") (pintype "passive"))
      (node (ref "POT4") (pin "3") (pinfunction "3_3") (pintype "passive"))
      (node (ref "POT6") (pin "3") (pinfunction "3_3") (pintype "passive"))
      (node (ref "R10") (pin "1") (pinfunction "1_1") (pintype "passive"))
      (node (ref "R13") (pin "1") (pinfunction "1_1") (pintype "passive"))
      (node (ref "R14") (pin "1") (pinfunction "1_1") (pintype "passive"))
      (node (ref "R15") (pin "1") (pinfunction "1_1") (pintype "passive"))
      (node (ref "R3") (pin "1") (pinfunction "1_1") (pintype "passive"))
      (node (ref "R4") (pin "1") (pinfunction "1_1") (pintype "passive"))
      (node (ref "R5") (pin "1") (pinfunction "1_1") (pintype "passive"))
      (node (ref "R8") (pin "1") (pinfunction "1_1") (pintype "passive"))
      (node (ref "R9") (pin "1") (pinfunction "1_1") (pintype "passive"))
      (node (ref "U1") (pin "14") (pinfunction "GND_14") (pintype "passive"))
      (node (ref "U1") (pin "28") (pinfunction "GND_2_28") (pintype "passive"))
      (node (ref "U1") (pin "29") (pinfunction "EPAD_29") (pintype "passive"))
      (node (ref "U2") (pin "14") (pinfunction "GND_14") (pintype "passive"))
      (node (ref "U2") (pin "28") (pinfunction "GND_2_28") (pintype "passive"))
      (node (ref "U2") (pin "29") (pinfunction "EPAD_29") (pintype "passive"))
      (node (ref "U3") (pin "14") (pinfunction "GND_14") (pintype "passive"))
      (node (ref "U3") (pin "28") (pinfunction "GND_2_28") (pintype "passive"))
      (node (ref "U3") (pin "29") (pinfunction "EPAD_29") (pintype "passive"))
    )
    (net (code "70") (name "N$6") (class "Default")
      (node (ref "A2") (pin "2") (pinfunction "P$2_2") (pintype "bidirectional"))
    )
    (net (code "71") (name "N$7") (class "Default")
      (node (ref "A2") (pin "3") (pinfunction "P$3_3") (pintype "bidirectional"))
    )
    (net (code "72") (name "N$8") (class "Default")
      (node (ref "A2") (pin "4") (pinfunction "P$4_4") (pintype "bidirectional"))
    )
    (net (code "73") (name "N$9") (class "Default")
      (node (ref "A2") (pin "5") (pinfunction "P$5_5") (pintype "bidirectional"))
    )
    (net (code "74") (name "N$10") (class "Default")
      (node (ref "A2") (pin "6") (pinfunction "P$6_6") (pintype "bidirectional"))
    )
    (net (code "75") (name "N$11") (class "Default")
      (node (ref "A2") (pin "7") (pinfunction "P$7_7") (pintype "bidirectional"))
    )
    (net (code "76") (name "N$12") (class "Default")
      (node (ref "A2") (pin "8") (pinfunction "P$8_8") (pintype "bidirectional"))
    )
    (net (code "77") (name "N$13") (class "Default")
      (node (ref "A2") (pin "9") (pinfunction "P$9_9") (pintype "bidirectional"))
    )
    (net (code "78") (name "N$14") (class "Default")
      (node (ref "A2") (pin "10") (pinfunction "P$10_10") (pintype "bidirectional"))
    )
    (net (code "79") (name "N$22") (class "Default")
      (node (ref "A2") (pin "28") (pinfunction "P$28_28") (pintype "bidirectional"))
    )
    (net (code "80") (name "N$23") (class "Default")
      (node (ref "A2") (pin "29") (pinfunction "P$29_29") (pintype "bidirectional"))
    )
    (net (code "81") (name "N$24") (class "Default")
      (node (ref "A2") (pin "30") (pinfunction "P$30_30") (pintype "bidirectional"))
    )
    (net (code "83") (name "N$35") (class "Default")
      (node (ref "A2") (pin "20") (pinfunction "P$20_20") (pintype "bidirectional"))
    )
    (net (code "84") (name "N$37") (class "Default")
      (node (ref "A2") (pin "18") (pinfunction "P$18_18") (pintype "bidirectional"))
    )
    (net (code "85") (name "N$38") (class "Default")
      (node (ref "A2") (pin "17") (pinfunction "P$17_17") (pintype "bidirectional"))
    )
    (net (code "86") (name "N$39") (class "Default")
      (node (ref "A2") (pin "16") (pinfunction "P$16_16") (pintype "bidirectional"))
    )
    (net (code "91") (name "Net-(U1-CP1)") (class "Default")
      (node (ref "C3") (pin "1") (pinfunction "1_1") (pintype "passive"))
      (node (ref "U1") (pin "1") (pinfunction "CP1_1") (pintype "bidirectional"))
    )
    (net (code "92") (name "Net-(U1-CP2)") (class "Default")
      (node (ref "C3") (pin "2") (pinfunction "2_2") (pintype "passive"))
      (node (ref "U1") (pin "2") (pinfunction "CP2_2") (pintype "bidirectional"))
    )
    (net (code "93") (name "Net-(U1-VCP)") (class "Default")
      (node (ref "C4") (pin "2") (pinfunction "2_2") (pintype "passive"))
      (node (ref "R1") (pin "1") (pinfunction "1_1") (pintype "passive"))
      (node (ref "U1") (pin "3") (pinfunction "VCP_3") (pintype "bidirectional"))
    )
    (net (code "94") (name "Net-(U2-CP1)") (class "Default")
      (node (ref "C24") (pin "1") (pinfunction "1_1") (pintype "passive"))
      (node (ref "U2") (pin "1") (pinfunction "CP1_1") (pintype "bidirectional"))
    )
    (net (code "95") (name "Net-(U2-CP2)") (class "Default")
      (node (ref "C24") (pin "2") (pinfunction "2_2") (pintype "passive"))
      (node (ref "U2") (pin "2") (pinfunction "CP2_2") (pintype "bidirectional"))
    )
    (net (code "96") (name "Net-(U2-VCP)") (class "Default")
      (node (ref "C25") (pin "2") (pinfunction "2_2") (pintype "passive"))
      (node (ref "R6") (pin "1") (pinfunction "1_1") (pintype "passive"))
      (node (ref "U2") (pin "3") (pinfunction "VCP_3") (pintype "bidirectional"))
    )
    (net (code "97") (name "Net-(U3-CP1)") (class "Default")
      (node (ref "C30") (pin "1") (pinfunction "1_1") (pintype "passive"))
      (node (ref "U3") (pin "1") (pinfunction "CP1_1") (pintype "bidirectional"))
    )
    (net (code "98") (name "Net-(U3-CP2)") (class "Default")
      (node (ref "C30") (pin "2") (pinfunction "2_2") (pintype "passive"))
      (node (ref "U3") (pin "2") (pinfunction "CP2_2") (pintype "bidirectional"))
    )
    (net (code "99") (name "Net-(U3-VCP)") (class "Default")
      (node (ref "C31") (pin "2") (pinfunction "2_2") (pintype "passive"))
      (node (ref "R11") (pin "1") (pinfunction "1_1") (pintype "passive"))
      (node (ref "U3") (pin "3") (pinfunction "VCP_3") (pintype "bidirectional"))
    )
    (net (code "100") (name "V+") (class "Default")
      (node (ref "5VREG") (pin "3") (pinfunction "IN_3") (pintype "input"))
      (node (ref "C1") (pin "1") (pinfunction "1_1") (pintype "passive"))
      (node (ref "C14") (pin "1") (pinfunction "1_1") (pintype "passive"))
      (node (ref "C2") (pin "1") (pinfunction "1_1") (pintype "passive"))
      (node (ref "C22") (pin "1") (pinfunction "1_1") (pintype "passive"))
      (node (ref "C23") (pin "1") (pinfunction "1_1") (pintype "passive"))
      (node (ref "C25") (pin "1") (pinfunction "1_1") (pintype "passive"))
      (node (ref "C26") (pin "1") (pinfunction "1_1") (pintype "passive"))
      (node (ref "C29") (pin "1") (pinfunction "1_1") (pintype "passive"))
      (node (ref "C31") (pin "1") (pinfunction "1_1") (pintype "passive"))
      (node (ref "C4") (pin "1") (pinfunction "1_1") (pintype "passive"))
      (node (ref "C5") (pin "+") (pinfunction "+_+") (pintype "passive"))
      (node (ref "GND|PWR") (pin "1") (pinfunction "1_1") (pintype "passive"))
      (node (ref "GND|PWR") (pin "2") (pinfunction "2_2") (pintype "passive"))
      (node (ref "R1") (pin "2") (pinfunction "2_2") (pintype "passive"))
      (node (ref "R11") (pin "2") (pinfunction "2_2") (pintype "passive"))
      (node (ref "R6") (pin "2") (pinfunction "2_2") (pintype "passive"))
      (node (ref "U1") (pin "11") (pinfunction "VMB_11") (pintype "power_in"))
      (node (ref "U1") (pin "4") (pinfunction "VMA_4") (pintype "power_in"))
      (node (ref "U2") (pin "11") (pinfunction "VMB_11") (pintype "power_in"))
      (node (ref "U2") (pin "4") (pinfunction "VMA_4") (pintype "power_in"))
      (node (ref "U3") (pin "11") (pinfunction "VMB_11") (pintype "power_in"))
      (node (ref "U3") (pin "4") (pinfunction "VMA_4") (pintype "power_in"))
    )
    (net (code "101") (name "unconnected-(A1-P$2-Pad2)") (class "Default")
      (node (ref "A1") (pin "2") (pinfunction "P$2_2") (pintype "bidirectional"))
    )
    (net (code "102") (name "unconnected-(A1-P$3-Pad3)") (class "Default")
      (node (ref "A1") (pin "3") (pinfunction "P$3_3") (pintype "bidirectional"))
    )
    (net (code "103") (name "unconnected-(A1-P$4-Pad4)") (class "Default")
      (node (ref "A1") (pin "4") (pinfunction "P$4_4") (pintype "bidirectional"))
    )
    (net (code "104") (name "unconnected-(A1-P$5-Pad5)") (class "Default")
      (node (ref "A1") (pin "5") (pinfunction "P$5_5") (pintype "bidirectional"))
    )
    (net (code "105") (name "unconnected-(A1-P$6-Pad6)") (class "Default")
      (node (ref "A1") (pin "6") (pinfunction "P$6_6") (pintype "bidirectional"))
    )
    (net (code "106") (name "unconnected-(A1-P$7-Pad7)") (class "Default")
      (node (ref "A1") (pin "7") (pinfunction "P$7_7") (pintype "bidirectional"))
    )
    (net (code "107") (name "unconnected-(A1-P$8-Pad8)") (class "Default")
      (node (ref "A1") (pin "8") (pinfunction "P$8_8") (pintype "bidirectional"))
    )
    (net (code "108") (name "unconnected-(A1-P$9-Pad9)") (class "Default")
      (node (ref "A1") (pin "9") (pinfunction "P$9_9") (pintype "bidirectional"))
    )
    (net (code "109") (name "unconnected-(A1-P$10-Pad10)") (class "Default")
      (node (ref "A1") (pin "10") (pinfunction "P$10_10") (pintype "bidirectional"))
    )
    (net (code "110") (name "unconnected-(A1-P$11-Pad11)") (class "Default")
      (node (ref "A1") (pin "11") (pinfunction "P$11_11") (pintype "bidirectional"))
    )
    (net (code "111") (name "unconnected-(A1-P$12-Pad12)") (class "Default")
      (node (ref "A1") (pin "12") (pinfunction "P$12_12") (pintype "bidirectional"))
    )
    (net (code "112") (name "unconnected-(A1-P$13-Pad13)") (class "Default")
      (node (ref "A1") (pin "13") (pinfunction "P$13_13") (pintype "bidirectional"))
    )
    (net (code "113") (name "unconnected-(A1-P$14-Pad14)") (class "Default")
      (node (ref "A1") (pin "14") (pinfunction "P$14_14") (pintype "bidirectional"))
    )
    (net (code "114") (name "unconnected-(A1-P$16-Pad16)") (class "Default")
      (node (ref "A1") (pin "16") (pinfunction "P$16_16") (pintype "bidirectional"))
    )
    (net (code "115") (name "unconnected-(A1-P$17-Pad17)") (class "Default")
      (node (ref "A1") (pin "17") (pinfunction "P$17_17") (pintype "bidirectional"))
    )
    (net (code "116") (name "unconnected-(A1-P$18-Pad18)") (class "Default")
      (node (ref "A1") (pin "18") (pinfunction "P$18_18") (pintype "bidirectional"))
    )
    (net (code "117") (name "unconnected-(A1-P$23-Pad23)") (class "Default")
      (node (ref "A1") (pin "23") (pinfunction "P$23_23") (pintype "bidirectional"))
    )
    (net (code "118") (name "unconnected-(A1-P$24-Pad24)") (class "Default")
      (node (ref "A1") (pin "24") (pinfunction "P$24_24") (pintype "bidirectional"))
    )
    (net (code "119") (name "unconnected-(A1-P$25-Pad25)") (class "Default")
      (node (ref "A1") (pin "25") (pinfunction "P$25_25") (pintype "bidirectional"))
    )
    (net (code "120") (name "unconnected-(A1-P$26-Pad26)") (class "Default")
      (node (ref "A1") (pin "26") (pinfunction "P$26_26") (pintype "bidirectional"))
    )
    (net (code "121") (name "unconnected-(A1-P$27-Pad27)") (class "Default")
      (node (ref "A1") (pin "27") (pinfunction "P$27_27") (pintype "bidirectional"))
    )
    (net (code "122") (name "unconnected-(A1-P$28-Pad28)") (class "Default")
      (node (ref "A1") (pin "28") (pinfunction "P$28_28") (pintype "bidirectional"))
    )
    (net (code "123") (name "unconnected-(A1-P$29-Pad29)") (class "Default")
      (node (ref "A1") (pin "29") (pinfunction "P$29_29") (pintype "bidirectional"))
    )
    (net (code "124") (name "unconnected-(A1-P$30-Pad30)") (class "Default")
      (node (ref "A1") (pin "30") (pinfunction "P$30_30") (pintype "bidirectional"))
    )
    (net (code "125") (name "unconnected-(A1-P$31-Pad31)") (class "Default")
      (node (ref "A1") (pin "31") (pinfunction "P$31_31") (pintype "bidirectional"))
    )
    (net (code "126") (name "unconnected-(A2-P$32-Pad32)") (class "Default")
      (node (ref "A2") (pin "32") (pinfunction "P$32_32") (pintype "bidirectional"))
    )
  )
)
